# DC-DC_10-40V_8A.net
KiCad netlist of a schematic drawn in Altium Designer
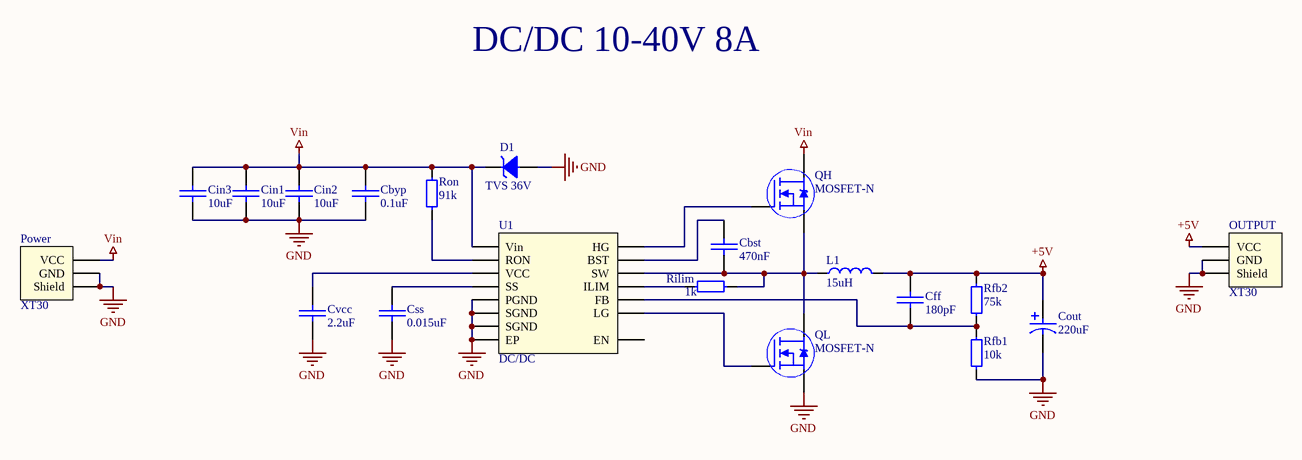
[diagram p0: DC-DC_10-40V_8A.SchDoc]

(export (version "E")
  (design (tool "Eeschema 10.0.6"))
  (components
    (comp (ref "Cbst")
      (value "470nF")
      (footprint "0603 Capicator")
      (description "470nF X7R 25V 10% 0603")
      (fields
        (field (name "MANUFACTURER") "Murata Manufacturing")
        (field (name "PART NUMBER") "GRM188R71E474KA12D")
      )
      (libsource (lib "Karen_Components") (part "Cap 470nF (0603)"))
    )
    (comp (ref "Cbyp")
      (value "0.1uF")
      (footprint "0603 Capicator")
      (description "0.1uF X7R 50V 10% 0603")
      (fields
        (field (name "MANUFACTURER") "Murata Manufacturing")
        (field (name "PART NUMBER") "GRM188R71H104KA93D")
      )
      (libsource (lib "Karen_Components") (part "Cap 0.1uF (0603)"))
    )
    (comp (ref "Cff")
      (value "180pF")
      (footprint "0603 Capicator")
      (description "180pF NP0 50V 5% 0603")
      (fields
        (field (name "MANUFACTURER") "Murata Manufacturing")
        (field (name "PART NUMBER") "GRM1885C1H181JA01D")
      )
      (libsource (lib "Karen_Components") (part "Cap 180pF (0603)"))
    )
    (comp (ref "Cin1")
      (value "10uF")
      (footprint "0603 Capicator")
      (description "10uF X5R 25V 20% 0603")
      (fields
        (field (name "MANUFACTURER") "Murata Manufacturing")
        (field (name "PART NUMBER") "GRM188R61E106M")
      )
      (libsource (lib "Karen_Components") (part "Cap 10uF (0603)"))
    )
    (comp (ref "Cin2")
      (value "10uF")
      (footprint "0603 Capicator")
      (description "10uF X5R 25V 20% 0603")
      (fields
        (field (name "MANUFACTURER") "Murata Manufacturing")
        (field (name "PART NUMBER") "GRM188R61E106M")
      )
      (libsource (lib "Karen_Components") (part "Cap 10uF (0603)"))
    )
    (comp (ref "Cin3")
      (value "10uF")
      (footprint "0603 Capicator")
      (description "10uF X5R 25V 20% 0603")
      (fields
        (field (name "MANUFACTURER") "Murata Manufacturing")
        (field (name "PART NUMBER") "GRM188R61E106M")
      )
      (libsource (lib "Karen_Components") (part "Cap 10uF (0603)"))
    )
    (comp (ref "Cout")
      (value "220uF")
      (footprint "Bar Cap 6.3x7.7")
      (description "ECAP SMD,  10V, 105°C, 20%")
      (fields (field (name "PART NUMBER") "JCK1A221M063077") (field (name "MANUFACTURER") "JB"))
      (libsource (lib "Karen_Components") (part "Cap Pol 220uF"))
    )
    (comp (ref "Css")
      (value "0.015uF")
      (footprint "0603 Capicator")
      (description "0.015uF X7R 50V 10% 0603")
      (fields (field (name "MANUFACTURER") "Taiwan") (field (name "PART NUMBER") "MLCC0.015uFX7R50V10%0603"))
      (libsource (lib "Karen_Components") (part "Cap 0.015uF (0603)"))
    )
    (comp (ref "Cvcc")
      (value "2.2uF")
      (footprint "0603 Capicator")
      (description "2.2uF X5R 10V 10% 0603")
      (fields
        (field (name "MANUFACTURER") "Murata Manufacturing")
        (field (name "PART NUMBER") "GRM188R61A225KE34D")
      )
      (libsource (lib "Karen_Components") (part "Cap 2.2uF (0603)"))
    )
    (comp (ref "D1")
      (value "TVS 36V")
      (footprint "SMB")
      (description "[SMB / DO-214AA], 600W")
      (fields (field (name "PART NUMBER") "SMBJ36CA-TR") (field (name "MANUFACTURER") "ST Microelectronics"))
      (libsource (lib "Karen_Components") (part "TVS Diode 36V (SMB)"))
    )
    (comp (ref "L1")
      (value "15uH")
      (footprint "Inductor 12.8 x 12.8 x 8.0")
      (description "[B82477G4153M], 15uH, 12.8x12.8, 4.5A")
      (fields (field (name "PART NUMBER") "B82477G4153M") (field (name "MANUFACTURER") "Epcos"))
      (libsource (lib "Karen_Components") (part "Inductor 15uH (4.5A)"))
    )
    (comp (ref "OUTPUT")
      (value "XT30")
      (footprint "HEADER 2 XT30PW FeMale")
      (fields (field (name "PART NUMBER") "XT30PW") (field (name "MANUFACTURER") "Amass"))
      (libsource (lib "Karen_Components") (part "Conn2x1 [XT30PW-Female]"))
    )
    (comp (ref "Power")
      (value "XT30")
      (footprint "HEADER 2 XT30PW Male")
      (fields (field (name "PART NUMBER") "XT30PW") (field (name "MANUFACTURER") "Amass"))
      (libsource (lib "Karen_Components") (part "Conn2x1 [XT30PW-Male]"))
    )
    (comp (ref "QH")
      (value "MOSFET-N")
      (footprint "VSON")
      (fields (field (name "PART NUMBER") "CSD19534Q5A") (field (name "MANUFACTURER") "Texas Instruments"))
      (libsource (lib "Karen_Components") (part "MOSFET-N [CSD]"))
    )
    (comp (ref "QL")
      (value "MOSFET-N")
      (footprint "VSON")
      (fields (field (name "PART NUMBER") "CSD19534Q5A") (field (name "MANUFACTURER") "Texas Instruments"))
      (libsource (lib "Karen_Components") (part "MOSFET-N [CSD]"))
    )
    (comp (ref "Rfb1")
      (value "10k")
      (footprint "0603 Resistor")
      (description "0.1W 0603 10k, 1%")
      (fields (field (name "PART NUMBER") "RC0603FR-0710KL") (field (name "MANUFACTURER") "Taiwan"))
      (libsource (lib "Karen_Components") (part "Res 10k (0603)"))
    )
    (comp (ref "Rfb2")
      (value "75k")
      (footprint "0603 Resistor")
      (description "0.1W 0603 75k, 1%")
      (fields (field (name "PART NUMBER") "RC0603FR-0775KL") (field (name "MANUFACTURER") "Taiwan"))
      (libsource (lib "Karen_Components") (part "Res 75k (0603)"))
    )
    (comp (ref "Rilim")
      (value "1k")
      (footprint "0603 Resistor")
      (description "0.1W 0603 1k, 1%")
      (fields (field (name "PART NUMBER") "RC0603FR-071KL") (field (name "MANUFACTURER") "Taiwan"))
      (libsource (lib "Karen_Components") (part "Res 1k (0603)"))
    )
    (comp (ref "Ron")
      (value "91k")
      (footprint "0603 Resistor")
      (description "0.1W 0603 91k, 1%")
      (fields (field (name "PART NUMBER") "RC0603FR-0791KL") (field (name "MANUFACTURER") "Taiwan"))
      (libsource (lib "Karen_Components") (part "Res 91k (0603)"))
    )
    (comp (ref "U1")
      (value "DC/DC")
      (footprint "HTSSOP-14")
      (fields (field (name "MANUFACTURER") "Texas Instruments") (field (name "PARTNUMBER") "LM3150MH/NOPB"))
      (libsource (lib "Karen_Components") (part "DC/DC Controller [LM3150]"))
    )
  )
  (nets
    (net (code "1") (name "+5V") (class "Default")
      (node (ref "Cff") (pin "2") (pinfunction "2_2") (pintype "passive"))
      (node (ref "Cout") (pin "2") (pinfunction "2_2") (pintype "passive"))
      (node (ref "L1") (pin "2") (pinfunction "2_2") (pintype "passive"))
      (node (ref "OUTPUT") (pin "2") (pinfunction "VCC_2") (pintype "passive"))
      (node (ref "Rfb2") (pin "2") (pinfunction "2_2") (pintype "passive"))
    )
    (net (code "2") (name "GND") (class "Default")
      (node (ref "Cbyp") (pin "2") (pinfunction "2_2") (pintype "passive"))
      (node (ref "Cin1") (pin "1") (pinfunction "1_1") (pintype "passive"))
      (node (ref "Cin2") (pin "1") (pinfunction "1_1") (pintype "passive"))
      (node (ref "Cin3") (pin "1") (pinfunction "1_1") (pintype "passive"))
      (node (ref "Cout") (pin "1") (pinfunction "1_1") (pintype "passive"))
      (node (ref "Css") (pin "1") (pinfunction "1_1") (pintype "passive"))
      (node (ref "Cvcc") (pin "2") (pinfunction "2_2") (pintype "passive"))
      (node (ref "D1") (pin "1") (pinfunction "1_1") (pintype "passive"))
      (node (ref "OUTPUT") (pin "1") (pinfunction "GND_1") (pintype "passive"))
      (node (ref "OUTPUT") (pin "A") (pinfunction "Shield_A") (pintype "passive"))
      (node (ref "Power") (pin "2") (pinfunction "GND_2") (pintype "passive"))
      (node (ref "Power") (pin "A") (pinfunction "Shield_A") (pintype "passive"))
      (node (ref "QL") (pin "3") (pinfunction "Sourse_3") (pintype "passive"))
      (node (ref "Rfb1") (pin "1") (pinfunction "1_1") (pintype "passive"))
      (node (ref "U1") (pin "14") (pinfunction "PGND_14") (pintype "power_in"))
      (node (ref "U1") (pin "5") (pinfunction "SGND_5") (pintype "power_in"))
      (node (ref "U1") (pin "9") (pinfunction "SGND_9") (pintype "power_in"))
      (node (ref "U1") (pin "A") (pinfunction "EP_A") (pintype "power_in"))
    )
    (net (code "3") (name "Net-(QH-Gate)") (class "Default")
      (node (ref "QH") (pin "1") (pinfunction "Gate_1") (pintype "passive"))
      (node (ref "U1") (pin "11") (pinfunction "HG_11") (pintype "passive"))
    )
    (net (code "4") (name "Net-(QH-Sourse)") (class "Default")
      (node (ref "Cbst") (pin "1") (pinfunction "1_1") (pintype "passive"))
      (node (ref "L1") (pin "1") (pinfunction "1_1") (pintype "passive"))
      (node (ref "QH") (pin "3") (pinfunction "Sourse_3") (pintype "passive"))
      (node (ref "QL") (pin "2") (pinfunction "Drain_2") (pintype "passive"))
      (node (ref "Rilim") (pin "2") (pinfunction "2_2") (pintype "passive"))
      (node (ref "U1") (pin "10") (pinfunction "SW_10") (pintype "passive"))
    )
    (net (code "5") (name "Net-(QL-Gate)") (class "Default")
      (node (ref "QL") (pin "1") (pinfunction "Gate_1") (pintype "passive"))
      (node (ref "U1") (pin "13") (pinfunction "LG_13") (pintype "passive"))
    )
    (net (code "6") (name "Net-(U1-BST)") (class "Default")
      (node (ref "Cbst") (pin "2") (pinfunction "2_2") (pintype "passive"))
      (node (ref "U1") (pin "12") (pinfunction "BST_12") (pintype "power_in"))
    )
    (net (code "7") (name "Net-(U1-FB)") (class "Default")
      (node (ref "Cff") (pin "1") (pinfunction "1_1") (pintype "passive"))
      (node (ref "Rfb1") (pin "2") (pinfunction "2_2") (pintype "passive"))
      (node (ref "Rfb2") (pin "1") (pinfunction "1_1") (pintype "passive"))
      (node (ref "U1") (pin "4") (pinfunction "FB_4") (pintype "passive"))
    )
    (net (code "8") (name "Net-(U1-ILIM)") (class "Default")
      (node (ref "Rilim") (pin "1") (pinfunction "1_1") (pintype "passive"))
      (node (ref "U1") (pin "8") (pinfunction "ILIM_8") (pintype "passive"))
    )
    (net (code "9") (name "Net-(U1-RON)") (class "Default")
      (node (ref "Ron") (pin "1") (pinfunction "1_1") (pintype "passive"))
      (node (ref "U1") (pin "7") (pinfunction "RON_7") (pintype "passive"))
    )
    (net (code "10") (name "Net-(U1-SS)") (class "Default")
      (node (ref "Css") (pin "2") (pinfunction "2_2") (pintype "passive"))
      (node (ref "U1") (pin "6") (pinfunction "SS_6") (pintype "open_collector"))
    )
    (net (code "11") (name "Net-(U1-VCC)") (class "Default")
      (node (ref "Cvcc") (pin "1") (pinfunction "1_1") (pintype "passive"))
      (node (ref "U1") (pin "1") (pinfunction "VCC_1") (pintype "power_in"))
    )
    (net (code "12") (name "Vin") (class "Default")
      (node (ref "Cbyp") (pin "1") (pinfunction "1_1") (pintype "passive"))
      (node (ref "Cin1") (pin "2") (pinfunction "2_2") (pintype "passive"))
      (node (ref "Cin2") (pin "2") (pinfunction "2_2") (pintype "passive"))
      (node (ref "Cin3") (pin "2") (pinfunction "2_2") (pintype "passive"))
      (node (ref "D1") (pin "2") (pinfunction "2_2") (pintype "passive"))
      (node (ref "Power") (pin "1") (pinfunction "VCC_1") (pintype "passive"))
      (node (ref "QH") (pin "2") (pinfunction "Drain_2") (pintype "passive"))
      (node (ref "Ron") (pin "2") (pinfunction "2_2") (pintype "passive"))
      (node (ref "U1") (pin "2") (pinfunction "Vin_2") (pintype "passive"))
    )
    (net (code "13") (name "unconnected-(U1-EN-Pad3)") (class "Default")
      (node (ref "U1") (pin "3") (pinfunction "EN_3") (pintype "passive"))
    )
  )
)
